# IOT_Fire_Alarm_Sheet.net
KiCad netlist of a schematic drawn in Altium Designer
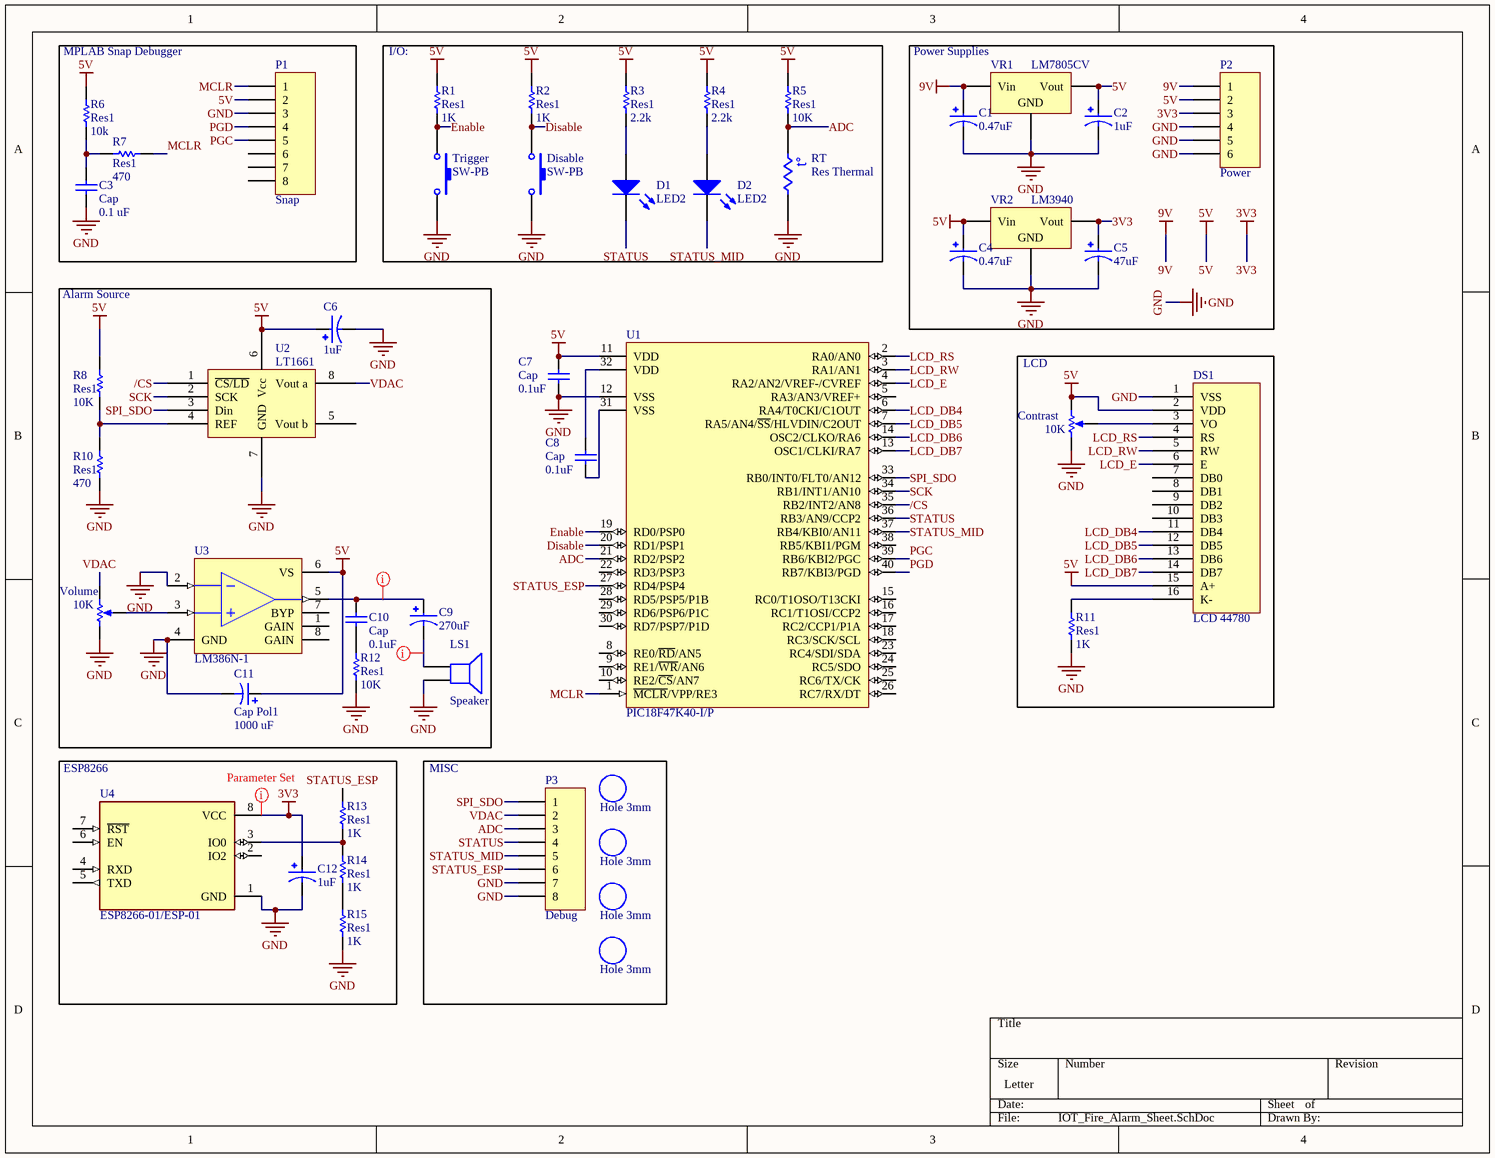
[diagram p0: IOT_Fire_Alarm_Sheet.SchDoc]

(export (version "E")
  (design (tool "Eeschema 10.0.6"))
  (components
    (comp (ref "C1")
      (value "0.47uF")
      (footprint "CAPPRD200W50D500H1500")
      (description "1F 63V Aluminum Electrolytic Capacitors Radial, Can 5000 Hrs @ 105C")
      (fields (field (name "MP") "EEU-EB1J1R0") (field (name "MF") "Panasonic Electronic Components"))
      (libsource (lib "EEUEB1J1R0") (part "EEUEB1J1R0"))
    )
    (comp (ref "C2")
      (value "1uF")
      (footprint "CAPPRD200W50D500H1500")
      (description "1F 63V Aluminum Electrolytic Capacitors Radial, Can 5000 Hrs @ 105C")
      (fields (field (name "MP") "EEU-EB1J1R0") (field (name "MF") "Panasonic Electronic Components"))
      (libsource (lib "EEUEB1J1R0") (part "EEUEB1J1R0"))
    )
    (comp (ref "C3")
      (value "Cap")
      (footprint "RAD-0.1")
      (description "Capacitor")
      (fields (field (name "ALTIUM_VALUE") "0.1 uF") (field (name "PUBLISHER") "Altium Limited"))
      (libsource (lib "Miscellaneous Devices") (part "Cap"))
    )
    (comp (ref "C4")
      (value "0.47uF")
      (footprint "CAPPRD200W50D500H1500")
      (description "1F 63V Aluminum Electrolytic Capacitors Radial, Can 5000 Hrs @ 105C")
      (fields (field (name "MP") "EEU-EB1J1R0") (field (name "MF") "Panasonic Electronic Components"))
      (libsource (lib "EEUEB1J1R0") (part "EEUEB1J1R0"))
    )
    (comp (ref "C5")
      (value "47uF")
      (footprint "CAPPRD200W50D500H1500")
      (description "1F 63V Aluminum Electrolytic Capacitors Radial, Can 5000 Hrs @ 105C")
      (fields (field (name "MP") "EEU-EB1J1R0") (field (name "MF") "Panasonic Electronic Components"))
      (libsource (lib "EEUEB1J1R0") (part "EEUEB1J1R0"))
    )
    (comp (ref "C6")
      (value "1uF")
      (footprint "CAPPRD200W50D500H1500")
      (description "1F 63V Aluminum Electrolytic Capacitors Radial, Can 5000 Hrs @ 105C")
      (fields (field (name "MP") "EEU-EB1J1R0") (field (name "MF") "Panasonic Electronic Components"))
      (libsource (lib "") (part "EEUEB1J1R0_1"))
    )
    (comp (ref "C7")
      (value "Cap")
      (footprint "RAD-0.1")
      (description "Capacitor")
      (fields (field (name "ALTIUM_VALUE") "0.1uF") (field (name "PUBLISHER") "Altium Limited"))
      (libsource (lib "Miscellaneous Devices") (part "Cap"))
    )
    (comp (ref "C8")
      (value "Cap")
      (footprint "RAD-0.1")
      (description "Capacitor")
      (fields (field (name "ALTIUM_VALUE") "0.1uF") (field (name "PUBLISHER") "Altium Limited"))
      (libsource (lib "Miscellaneous Devices") (part "Cap"))
    )
    (comp (ref "C9")
      (value "270uF")
      (footprint "CAPPRD500W60D1000H1250")
      (description "Capacitor; Aluminum Electrolytic; Radial Al Electrolytic Cap; 100uF 63V")
      (fields (field (name "MF") "Panasonic Electronic") (field (name "MP") "EEU-FC1J101"))
      (libsource (lib "EEUFC1J101") (part "EEUFC1J101"))
    )
    (comp (ref "C10")
      (value "Cap")
      (footprint "RAD-0.1")
      (description "Capacitor")
      (fields (field (name "ALTIUM_VALUE") "0.1uF") (field (name "PUBLISHER") "Altium Limited"))
      (libsource (lib "Miscellaneous Devices") (part "Cap"))
    )
    (comp (ref "C11")
      (value "Cap Pol1")
      (footprint "RB7.6-15")
      (description "Polarized Capacitor (Radial)")
      (fields (field (name "ALTIUM_VALUE") "1000 uF") (field (name "PUBLISHER") "Altium Limited"))
      (libsource (lib "Miscellaneous Devices") (part "Cap Pol1"))
    )
    (comp (ref "C12")
      (value "1uF")
      (footprint "CAPPRD200W50D500H1500")
      (description "1F 63V Aluminum Electrolytic Capacitors Radial, Can 5000 Hrs @ 105C")
      (fields (field (name "MP") "EEU-EB1J1R0") (field (name "MF") "Panasonic Electronic Components"))
      (libsource (lib "EEUEB1J1R0") (part "EEUEB1J1R0"))
    )
    (comp (ref "Contrast")
      (value "10K")
      (footprint "POT inline wide")
      (description "Potentiometer")
      (fields (field (name "Comment") "RPot_3") (field (name "PUBLISHER") "Altium Limited"))
      (libsource (lib "ECE LIB 21") (part "RPot"))
    )
    (comp (ref "D1")
      (value "LED2")
      (footprint "LED-1")
      (description "Typical RED, GREEN, YELLOW, AMBER GaAs LED")
      (fields (field (name "PUBLISHER") "Altium Limited"))
      (libsource (lib "Miscellaneous Devices") (part "LED2"))
    )
    (comp (ref "D2")
      (value "LED2")
      (footprint "LED-1")
      (description "Typical RED, GREEN, YELLOW, AMBER GaAs LED")
      (fields (field (name "PUBLISHER") "Altium Limited"))
      (libsource (lib "Miscellaneous Devices") (part "LED2"))
    )
    (comp (ref "Disable")
      (value "SW-PB")
      (footprint "SW PB")
      (description "DIGIKEY SW400-ND")
      (fields (field (name "PUBLISHER") "Altium Limited"))
      (libsource (lib "ECE LIB 21") (part "SW-PB"))
    )
    (comp (ref "DS1")
      (value "LCD 44780")
      (footprint "OLED 16x2")
      (libsource (lib "ECE LIB 21") (part "LCD 44780"))
    )
    (comp (ref "H1")
      (value "Hole 3mm")
      (footprint "Hole 3mm")
      (libsource (lib "ECE LIB 21") (part "Hole 3mm"))
    )
    (comp (ref "H2")
      (value "Hole 3mm")
      (footprint "Hole 3mm")
      (libsource (lib "ECE LIB 21") (part "Hole 3mm"))
    )
    (comp (ref "H3")
      (value "Hole 3mm")
      (footprint "Hole 3mm")
      (libsource (lib "ECE LIB 21") (part "Hole 3mm"))
    )
    (comp (ref "H4")
      (value "Hole 3mm")
      (footprint "Hole 3mm")
      (libsource (lib "ECE LIB 21") (part "Hole 3mm"))
    )
    (comp (ref "LS1")
      (value "Speaker")
      (footprint "PIN2")
      (description "Loudspeaker")
      (fields (field (name "PUBLISHER") "Altium Limited"))
      (libsource (lib "Miscellaneous Devices") (part "Speaker"))
    )
    (comp (ref "P1")
      (value "Snap")
      (footprint "HDR1X8")
      (description "Header, 8-Pin")
      (fields (field (name "PUBLISHER") "Altium Limited"))
      (libsource (lib "Miscellaneous Connectors") (part "Header 8"))
    )
    (comp (ref "P2")
      (value "Power")
      (footprint "HDR1X6")
      (description "Header, 6-Pin")
      (fields (field (name "PUBLISHER") "Altium Limited"))
      (libsource (lib "Miscellaneous Connectors") (part "Header 6"))
    )
    (comp (ref "P3")
      (value "Debug")
      (footprint "HDR1X8")
      (description "Header, 8-Pin")
      (fields (field (name "PUBLISHER") "Altium Limited"))
      (libsource (lib "Miscellaneous Connectors") (part "Header 8"))
    )
    (comp (ref "R1")
      (value "Res1")
      (footprint "AXIAL-0.3")
      (description "Resistor")
      (fields (field (name "ALTIUM_VALUE") "1K") (field (name "PUBLISHER") "Altium Limited"))
      (libsource (lib "Miscellaneous Devices") (part "Res1"))
    )
    (comp (ref "R2")
      (value "Res1")
      (footprint "AXIAL-0.3")
      (description "Resistor")
      (fields (field (name "ALTIUM_VALUE") "1K") (field (name "PUBLISHER") "Altium Limited"))
      (libsource (lib "Miscellaneous Devices") (part "Res1"))
    )
    (comp (ref "R3")
      (value "Res1")
      (footprint "AXIAL-0.3")
      (description "Resistor")
      (fields (field (name "ALTIUM_VALUE") "2.2k") (field (name "PUBLISHER") "Altium Limited"))
      (libsource (lib "Miscellaneous Devices") (part "Res1"))
    )
    (comp (ref "R4")
      (value "Res1")
      (footprint "AXIAL-0.3")
      (description "Resistor")
      (fields (field (name "ALTIUM_VALUE") "2.2k") (field (name "PUBLISHER") "Altium Limited"))
      (libsource (lib "Miscellaneous Devices") (part "Res1"))
    )
    (comp (ref "R5")
      (value "Res1")
      (footprint "AXIAL-0.3")
      (description "Resistor")
      (fields (field (name "ALTIUM_VALUE") "10K") (field (name "PUBLISHER") "Altium Limited"))
      (libsource (lib "Miscellaneous Devices") (part "Res1"))
    )
    (comp (ref "R6")
      (value "Res1")
      (footprint "AXIAL-0.3")
      (description "Resistor")
      (fields (field (name "ALTIUM_VALUE") "10k") (field (name "PUBLISHER") "Altium Limited"))
      (libsource (lib "Miscellaneous Devices") (part "Res1"))
    )
    (comp (ref "R7")
      (value "Res1")
      (footprint "AXIAL-0.3")
      (description "Resistor")
      (fields (field (name "ALTIUM_VALUE") "470") (field (name "PUBLISHER") "Altium Limited"))
      (libsource (lib "Miscellaneous Devices") (part "Res1"))
    )
    (comp (ref "R8")
      (value "Res1")
      (footprint "AXIAL-0.3")
      (description "Resistor")
      (fields (field (name "ALTIUM_VALUE") "10K") (field (name "PUBLISHER") "Altium Limited"))
      (libsource (lib "Miscellaneous Devices") (part "Res1"))
    )
    (comp (ref "R10")
      (value "Res1")
      (footprint "AXIAL-0.3")
      (description "Resistor")
      (fields (field (name "ALTIUM_VALUE") "470") (field (name "PUBLISHER") "Altium Limited"))
      (libsource (lib "Miscellaneous Devices") (part "Res1"))
    )
    (comp (ref "R11")
      (value "Res1")
      (footprint "AXIAL-0.3")
      (description "Resistor")
      (fields (field (name "ALTIUM_VALUE") "1K") (field (name "PUBLISHER") "Altium Limited"))
      (libsource (lib "Miscellaneous Devices") (part "Res1"))
    )
    (comp (ref "R12")
      (value "Res1")
      (footprint "AXIAL-0.3")
      (description "Resistor")
      (fields (field (name "ALTIUM_VALUE") "10K") (field (name "PUBLISHER") "Altium Limited"))
      (libsource (lib "Miscellaneous Devices") (part "Res1"))
    )
    (comp (ref "R13")
      (value "Res1")
      (footprint "AXIAL-0.3")
      (description "Resistor")
      (fields (field (name "ALTIUM_VALUE") "1K") (field (name "PUBLISHER") "Altium Limited"))
      (libsource (lib "Miscellaneous Devices") (part "Res1"))
    )
    (comp (ref "R14")
      (value "Res1")
      (footprint "AXIAL-0.3")
      (description "Resistor")
      (fields (field (name "ALTIUM_VALUE") "1K") (field (name "PUBLISHER") "Altium Limited"))
      (libsource (lib "Miscellaneous Devices") (part "Res1"))
    )
    (comp (ref "R15")
      (value "Res1")
      (footprint "AXIAL-0.3")
      (description "Resistor")
      (fields (field (name "ALTIUM_VALUE") "1K") (field (name "PUBLISHER") "Altium Limited"))
      (libsource (lib "Miscellaneous Devices") (part "Res1"))
    )
    (comp (ref "RT")
      (value "Res Thermal")
      (footprint "RAD-0.2")
      (description "Thermistor")
      (fields (field (name "PUBLISHER") "Altium Limited"))
      (libsource (lib "Miscellaneous Devices") (part "Res Thermal"))
    )
    (comp (ref "Trigger")
      (value "SW-PB")
      (footprint "SW PB")
      (description "DIGIKEY SW400-ND")
      (fields (field (name "PUBLISHER") "Altium Limited"))
      (libsource (lib "ECE LIB 21") (part "SW-PB"))
    )
    (comp (ref "U1")
      (value "PIC18F47K40-I/P")
      (footprint "DIP-40")
      (libsource (lib "ECE LIB 21") (part "PIC18F4620-I/P_1"))
    )
    (comp (ref "U2") (value "LT1661") (footprint "DIP-8") (libsource (lib "ECE LIB 21") (part "LT1661")))
    (comp (ref "U3")
      (value "LM386N-1")
      (footprint "DIP-8")
      (description "Low-Voltage Audio Power Amplifier")
      (fields (field (name "PUBLISHER") "Altium Limited"))
      (libsource (lib "ECE LIB 21") (part "LM386N-1"))
    )
    (comp (ref "U4")
      (value "ESP8266-01/ESP-01")
      (footprint "XCVR_ESP8266-01/ESP-01")
      (fields (field (name "MF") "AI-Thinker"))
      (libsource (lib "ESP8266-01_ESP-01") (part "ESP8266-01/ESP-01"))
    )
    (comp (ref "Volume")
      (value "10K")
      (footprint "POT inline wide")
      (description "Potentiometer")
      (fields (field (name "Comment") "RPot_3") (field (name "PUBLISHER") "Altium Limited"))
      (libsource (lib "ECE LIB 21") (part "RPot"))
    )
    (comp (ref "VR1")
      (value "LM7805CV")
      (footprint "T03B")
      (description "Voltage Regulator")
      (fields (field (name "PUBLISHER") "Altium Limited"))
      (libsource (lib "Miscellaneous Devices") (part "Volt Reg"))
    )
    (comp (ref "VR2")
      (value "LM3940")
      (footprint "T03B")
      (description "Voltage Regulator")
      (fields (field (name "PUBLISHER") "Altium Limited"))
      (libsource (lib "Miscellaneous Devices") (part "Volt Reg"))
    )
  )
  (nets
    (net (code "1") (name "/ADC") (class "Default")
      (node (ref "P3") (pin "3") (pinfunction "3_3") (pintype "passive"))
      (node (ref "R5") (pin "1") (pinfunction "1_1") (pintype "passive"))
      (node (ref "RT") (pin "1") (pinfunction "1_1") (pintype "passive"))
      (node (ref "U1") (pin "21") (pinfunction "RD2/PSP2_21") (pintype "bidirectional"))
    )
    (net (code "2") (name "/Disable") (class "Default")
      (node (ref "Disable") (pin "1") (pinfunction "1_1") (pintype "passive"))
      (node (ref "R2") (pin "1") (pinfunction "1_1") (pintype "passive"))
      (node (ref "U1") (pin "20") (pinfunction "RD1/PSP1_20") (pintype "bidirectional"))
    )
    (net (code "3") (name "/Enable") (class "Default")
      (node (ref "R1") (pin "1") (pinfunction "1_1") (pintype "passive"))
      (node (ref "Trigger") (pin "1") (pinfunction "1_1") (pintype "passive"))
      (node (ref "U1") (pin "19") (pinfunction "RD0/PSP0_19") (pintype "bidirectional"))
    )
    (net (code "4") (name "/LCD_DB4") (class "Default")
      (node (ref "DS1") (pin "11") (pinfunction "DB4_11") (pintype "passive"))
      (node (ref "U1") (pin "6") (pinfunction "RA4/T0CKI/C1OUT_6") (pintype "bidirectional"))
    )
    (net (code "5") (name "/LCD_DB5") (class "Default")
      (node (ref "DS1") (pin "12") (pinfunction "DB5_12") (pintype "passive"))
      (node (ref "U1") (pin "7") (pinfunction "RA5/AN4/~{SS}/HLVDIN/C2OUT_7") (pintype "bidirectional"))
    )
    (net (code "6") (name "/LCD_DB6") (class "Default")
      (node (ref "DS1") (pin "13") (pinfunction "DB6_13") (pintype "passive"))
      (node (ref "U1") (pin "14") (pinfunction "OSC2/CLKO/RA6_14") (pintype "bidirectional"))
    )
    (net (code "7") (name "/LCD_DB7") (class "Default")
      (node (ref "DS1") (pin "14") (pinfunction "DB7_14") (pintype "passive"))
      (node (ref "U1") (pin "13") (pinfunction "OSC1/CLKI/RA7_13") (pintype "bidirectional"))
    )
    (net (code "8") (name "/LCD_E") (class "Default")
      (node (ref "DS1") (pin "6") (pinfunction "E_6") (pintype "passive"))
      (node (ref "U1") (pin "4") (pinfunction "RA2/AN2/VREF-/CVREF_4") (pintype "bidirectional"))
    )
    (net (code "9") (name "/LCD_RS") (class "Default")
      (node (ref "DS1") (pin "4") (pinfunction "RS_4") (pintype "passive"))
      (node (ref "U1") (pin "2") (pinfunction "RA0/AN0_2") (pintype "bidirectional"))
    )
    (net (code "10") (name "/LCD_RW") (class "Default")
      (node (ref "DS1") (pin "5") (pinfunction "RW_5") (pintype "passive"))
      (node (ref "U1") (pin "3") (pinfunction "RA1/AN1_3") (pintype "bidirectional"))
    )
    (net (code "11") (name "/MCLR") (class "Default")
      (node (ref "P1") (pin "1") (pinfunction "1_1") (pintype "passive"))
      (node (ref "R7") (pin "2") (pinfunction "2_2") (pintype "passive"))
      (node (ref "U1") (pin "1") (pinfunction "~{MCLR}/VPP/RE3_1") (pintype "input"))
    )
    (net (code "12") (name "/PGC") (class "Default")
      (node (ref "P1") (pin "5") (pinfunction "5_5") (pintype "passive"))
      (node (ref "U1") (pin "39") (pinfunction "RB6/KBI2/PGC_39") (pintype "bidirectional"))
    )
    (net (code "13") (name "/PGD") (class "Default")
      (node (ref "P1") (pin "4") (pinfunction "4_4") (pintype "passive"))
      (node (ref "U1") (pin "40") (pinfunction "RB7/KBI3/PGD_40") (pintype "bidirectional"))
    )
    (net (code "14") (name "/SCK") (class "Default")
      (node (ref "U1") (pin "34") (pinfunction "RB1/INT1/AN10_34") (pintype "bidirectional"))
      (node (ref "U2") (pin "2") (pinfunction "SCK_2") (pintype "passive"))
    )
    (net (code "15") (name "/SPI_SDO") (class "Default")
      (node (ref "P3") (pin "1") (pinfunction "1_1") (pintype "passive"))
      (node (ref "U1") (pin "33") (pinfunction "RB0/INT0/FLT0/AN12_33") (pintype "bidirectional"))
      (node (ref "U2") (pin "3") (pinfunction "Din_3") (pintype "passive"))
    )
    (net (code "16") (name "/STATUS") (class "Default")
      (node (ref "D1") (pin "2") (pinfunction "K_2") (pintype "passive"))
      (node (ref "P3") (pin "4") (pinfunction "4_4") (pintype "passive"))
      (node (ref "U1") (pin "36") (pinfunction "RB3/AN9/CCP2_36") (pintype "bidirectional"))
    )
    (net (code "17") (name "/STATUS_ESP") (class "Default")
      (node (ref "P3") (pin "6") (pinfunction "6_6") (pintype "passive"))
      (node (ref "R13") (pin "2") (pinfunction "2_2") (pintype "passive"))
      (node (ref "U1") (pin "27") (pinfunction "RD4/PSP4_27") (pintype "bidirectional"))
    )
    (net (code "18") (name "/STATUS_MID") (class "Default")
      (node (ref "D2") (pin "2") (pinfunction "K_2") (pintype "passive"))
      (node (ref "P3") (pin "5") (pinfunction "5_5") (pintype "passive"))
      (node (ref "U1") (pin "37") (pinfunction "RB4/KBI0/AN11_37") (pintype "bidirectional"))
    )
    (net (code "19") (name "/VDAC") (class "Default")
      (node (ref "P3") (pin "2") (pinfunction "2_2") (pintype "passive"))
      (node (ref "U2") (pin "8") (pinfunction "Vout_a_8") (pintype "passive"))
      (node (ref "Volume") (pin "3") (pinfunction "BOT_3") (pintype "passive"))
    )
    (net (code "20") (name "/{slash}CS") (class "Default")
      (node (ref "U1") (pin "35") (pinfunction "RB2/INT2/AN8_35") (pintype "bidirectional"))
      (node (ref "U2") (pin "1") (pinfunction "~{CS/LD}_1") (pintype "passive"))
    )
    (net (code "21") (name "3V3") (class "Default")
      (node (ref "C12") (pin "P") (pinfunction "P_P") (pintype "passive"))
      (node (ref "C5") (pin "P") (pinfunction "P_P") (pintype "passive"))
      (node (ref "P2") (pin "3") (pinfunction "3_3") (pintype "passive"))
      (node (ref "U4") (pin "8") (pinfunction "VCC_8") (pintype "power_in"))
      (node (ref "VR2") (pin "3") (pinfunction "Vout_3") (pintype "passive"))
    )
    (net (code "22") (name "5V") (class "Default")
      (node (ref "C11") (pin "1") (pinfunction "1_1") (pintype "passive"))
      (node (ref "C2") (pin "P") (pinfunction "P_P") (pintype "passive"))
      (node (ref "C4") (pin "P") (pinfunction "P_P") (pintype "passive"))
      (node (ref "C6") (pin "P") (pinfunction "P_P") (pintype "passive"))
      (node (ref "C7") (pin "2") (pinfunction "2_2") (pintype "passive"))
      (node (ref "Contrast") (pin "3") (pinfunction "BOT_3") (pintype "passive"))
      (node (ref "DS1") (pin "15") (pinfunction "A+_15") (pintype "passive"))
      (node (ref "DS1") (pin "2") (pinfunction "VDD_2") (pintype "passive"))
      (node (ref "P1") (pin "2") (pinfunction "2_2") (pintype "passive"))
      (node (ref "P2") (pin "2") (pinfunction "2_2") (pintype "passive"))
      (node (ref "R1") (pin "2") (pinfunction "2_2") (pintype "passive"))
      (node (ref "R2") (pin "2") (pinfunction "2_2") (pintype "passive"))
      (node (ref "R3") (pin "2") (pinfunction "2_2") (pintype "passive"))
      (node (ref "R4") (pin "2") (pinfunction "2_2") (pintype "passive"))
      (node (ref "R5") (pin "2") (pinfunction "2_2") (pintype "passive"))
      (node (ref "R6") (pin "2") (pinfunction "2_2") (pintype "passive"))
      (node (ref "R8") (pin "1") (pinfunction "1_1") (pintype "passive"))
      (node (ref "U1") (pin "11") (pinfunction "VDD_11") (pintype "power_in"))
      (node (ref "U2") (pin "6") (pinfunction "Vcc_6") (pintype "passive"))
      (node (ref "U3") (pin "6") (pinfunction "VS_6") (pintype "power_in"))
      (node (ref "VR1") (pin "3") (pinfunction "Vout_3") (pintype "passive"))
      (node (ref "VR2") (pin "1") (pinfunction "Vin_1") (pintype "passive"))
    )
    (net (code "23") (name "9V") (class "Default")
      (node (ref "C1") (pin "P") (pinfunction "P_P") (pintype "passive"))
      (node (ref "P2") (pin "1") (pinfunction "1_1") (pintype "passive"))
      (node (ref "VR1") (pin "1") (pinfunction "Vin_1") (pintype "passive"))
    )
    (net (code "24") (name "GND") (class "Default")
      (node (ref "C1") (pin "N") (pinfunction "N_N") (pintype "passive"))
      (node (ref "C11") (pin "2") (pinfunction "2_2") (pintype "passive"))
      (node (ref "C12") (pin "N") (pinfunction "N_N") (pintype "passive"))
      (node (ref "C2") (pin "N") (pinfunction "N_N") (pintype "passive"))
      (node (ref "C3") (pin "1") (pinfunction "1_1") (pintype "passive"))
      (node (ref "C4") (pin "N") (pinfunction "N_N") (pintype "passive"))
      (node (ref "C5") (pin "N") (pinfunction "N_N") (pintype "passive"))
      (node (ref "C6") (pin "N") (pinfunction "N_N") (pintype "passive"))
      (node (ref "C7") (pin "1") (pinfunction "1_1") (pintype "passive"))
      (node (ref "Contrast") (pin "1") (pinfunction "TOP_1") (pintype "passive"))
      (node (ref "DS1") (pin "1") (pinfunction "VSS_1") (pintype "passive"))
      (node (ref "Disable") (pin "2") (pinfunction "2_2") (pintype "passive"))
      (node (ref "LS1") (pin "2") (pinfunction "2_2") (pintype "passive"))
      (node (ref "P1") (pin "3") (pinfunction "3_3") (pintype "passive"))
      (node (ref "P2") (pin "4") (pinfunction "4_4") (pintype "passive"))
      (node (ref "P2") (pin "5") (pinfunction "5_5") (pintype "passive"))
      (node (ref "P2") (pin "6") (pinfunction "6_6") (pintype "passive"))
      (node (ref "P3") (pin "7") (pinfunction "7_7") (pintype "passive"))
      (node (ref "P3") (pin "8") (pinfunction "8_8") (pintype "passive"))
      (node (ref "R10") (pin "1") (pinfunction "1_1") (pintype "passive"))
      (node (ref "R11") (pin "1") (pinfunction "1_1") (pintype "passive"))
      (node (ref "R12") (pin "1") (pinfunction "1_1") (pintype "passive"))
      (node (ref "R15") (pin "1") (pinfunction "1_1") (pintype "passive"))
      (node (ref "RT") (pin "2") (pinfunction "2_2") (pintype "passive"))
      (node (ref "Trigger") (pin "2") (pinfunction "2_2") (pintype "passive"))
      (node (ref "U1") (pin "12") (pinfunction "VSS_12") (pintype "power_in"))
      (node (ref "U2") (pin "7") (pinfunction "GND_7") (pintype "passive"))
      (node (ref "U3") (pin "2") (pinfunction "IN-_2") (pintype "input"))
      (node (ref "U3") (pin "4") (pinfunction "GND_4") (pintype "power_in"))
      (node (ref "U4") (pin "1") (pinfunction "GND_1") (pintype "power_in"))
      (node (ref "VR1") (pin "2") (pinfunction "GND_2") (pintype "passive"))
      (node (ref "VR2") (pin "2") (pinfunction "GND_2") (pintype "passive"))
      (node (ref "Volume") (pin "1") (pinfunction "TOP_1") (pintype "passive"))
    )
    (net (code "25") (name "Net-(C3-Pad2)") (class "Default")
      (node (ref "C3") (pin "2") (pinfunction "2_2") (pintype "passive"))
      (node (ref "R6") (pin "1") (pinfunction "1_1") (pintype "passive"))
      (node (ref "R7") (pin "1") (pinfunction "1_1") (pintype "passive"))
    )
    (net (code "26") (name "Net-(C8-Pad1)") (class "Default")
      (node (ref "C8") (pin "1") (pinfunction "1_1") (pintype "passive"))
      (node (ref "U1") (pin "31") (pinfunction "VSS_31") (pintype "power_in"))
    )
    (net (code "27") (name "Net-(C8-Pad2)") (class "Default")
      (node (ref "C8") (pin "2") (pinfunction "2_2") (pintype "passive"))
      (node (ref "U1") (pin "32") (pinfunction "VDD_32") (pintype "power_in"))
    )
    (net (code "28") (name "Net-(C9-PadN)") (class "Default")
      (node (ref "C9") (pin "N") (pinfunction "N_N") (pintype "passive"))
      (node (ref "LS1") (pin "1") (pinfunction "1_1") (pintype "passive"))
    )
    (net (code "29") (name "Net-(C10-Pad1)") (class "Default")
      (node (ref "C10") (pin "1") (pinfunction "1_1") (pintype "passive"))
      (node (ref "R12") (pin "2") (pinfunction "2_2") (pintype "passive"))
    )
    (net (code "30") (name "Net-(Contrast-TAP)") (class "Default")
      (node (ref "Contrast") (pin "2") (pinfunction "TAP_2") (pintype "passive"))
      (node (ref "DS1") (pin "3") (pinfunction "VO_3") (pintype "passive"))
    )
    (net (code "31") (name "Net-(D1-A)") (class "Default")
      (node (ref "D1") (pin "1") (pinfunction "A_1") (pintype "passive"))
      (node (ref "R3") (pin "1") (pinfunction "1_1") (pintype "passive"))
    )
    (net (code "32") (name "Net-(D2-A)") (class "Default")
      (node (ref "D2") (pin "1") (pinfunction "A_1") (pintype "passive"))
      (node (ref "R4") (pin "1") (pinfunction "1_1") (pintype "passive"))
    )
    (net (code "33") (name "Net-(DS1-K-)") (class "Default")
      (node (ref "DS1") (pin "16") (pinfunction "K-_16") (pintype "passive"))
      (node (ref "R11") (pin "2") (pinfunction "2_2") (pintype "passive"))
    )
    (net (code "34") (name "Net-(R14-Pad1)") (class "Default")
      (node (ref "R14") (pin "1") (pinfunction "1_1") (pintype "passive"))
      (node (ref "R15") (pin "2") (pinfunction "2_2") (pintype "passive"))
    )
    (net (code "35") (name "Net-(U2-REF)") (class "Default")
      (node (ref "R10") (pin "2") (pinfunction "2_2") (pintype "passive"))
      (node (ref "R8") (pin "2") (pinfunction "2_2") (pintype "passive"))
      (node (ref "U2") (pin "4") (pinfunction "REF_4") (pintype "passive"))
    )
    (net (code "36") (name "Net-(U3-IN+)") (class "Default")
      (node (ref "U3") (pin "3") (pinfunction "IN+_3") (pintype "input"))
      (node (ref "Volume") (pin "2") (pinfunction "TAP_2") (pintype "passive"))
    )
    (net (code "37") (name "Net-(U3-OUT)") (class "Default")
      (node (ref "C10") (pin "2") (pinfunction "2_2") (pintype "passive"))
      (node (ref "C9") (pin "P") (pinfunction "P_P") (pintype "passive"))
      (node (ref "U3") (pin "5") (pinfunction "OUT_5") (pintype "output"))
    )
    (net (code "38") (name "Net-(U4-IO0)") (class "Default")
      (node (ref "R13") (pin "1") (pinfunction "1_1") (pintype "passive"))
      (node (ref "R14") (pin "2") (pinfunction "2_2") (pintype "passive"))
      (node (ref "U4") (pin "3") (pinfunction "IO0_3") (pintype "bidirectional"))
    )
    (net (code "39") (name "unconnected-(DS1-DB0-Pad7)") (class "Default")
      (node (ref "DS1") (pin "7") (pinfunction "DB0_7") (pintype "passive"))
    )
    (net (code "40") (name "unconnected-(DS1-DB1-Pad8)") (class "Default")
      (node (ref "DS1") (pin "8") (pinfunction "DB1_8") (pintype "passive"))
    )
    (net (code "41") (name "unconnected-(DS1-DB2-Pad9)") (class "Default")
      (node (ref "DS1") (pin "9") (pinfunction "DB2_9") (pintype "passive"))
    )
    (net (code "42") (name "unconnected-(DS1-DB3-Pad10)") (class "Default")
      (node (ref "DS1") (pin "10") (pinfunction "DB3_10") (pintype "passive"))
    )
    (net (code "43") (name "unconnected-(P1-Pad6)") (class "Default")
      (node (ref "P1") (pin "6") (pinfunction "6_6") (pintype "passive"))
    )
    (net (code "44") (name "unconnected-(P1-Pad7)") (class "Default")
      (node (ref "P1") (pin "7") (pinfunction "7_7") (pintype "passive"))
    )
    (net (code "45") (name "unconnected-(P1-Pad8)") (class "Default")
      (node (ref "P1") (pin "8") (pinfunction "8_8") (pintype "passive"))
    )
    (net (code "46") (name "unconnected-(U1-RA3{slash}AN3{slash}VREF+-Pad5)") (class "Default")
      (node (ref "U1") (pin "5") (pinfunction "RA3/AN3/VREF+_5") (pintype "bidirectional"))
    )
    (net (code "47") (name "unconnected-(U1-RB5{slash}KBI1{slash}PGM-Pad38)") (class "Default")
      (node (ref "U1") (pin "38") (pinfunction "RB5/KBI1/PGM_38") (pintype "bidirectional"))
    )
    (net (code "48") (name "unconnected-(U1-RC0{slash}T1OSO{slash}T13CKI-Pad15)") (class "Default")
      (node (ref "U1") (pin "15") (pinfunction "RC0/T1OSO/T13CKI_15") (pintype "bidirectional"))
    )
    (net (code "49") (name "unconnected-(U1-RC1{slash}T1OSI{slash}CCP2-Pad16)") (class "Default")
      (node (ref "U1") (pin "16") (pinfunction "RC1/T1OSI/CCP2_16") (pintype "bidirectional"))
    )
    (net (code "50") (name "unconnected-(U1-RC2{slash}CCP1{slash}P1A-Pad17)") (class "Default")
      (node (ref "U1") (pin "17") (pinfunction "RC2/CCP1/P1A_17") (pintype "bidirectional"))
    )
    (net (code "51") (name "unconnected-(U1-RC3{slash}SCK{slash}SCL-Pad18)") (class "Default")
      (node (ref "U1") (pin "18") (pinfunction "RC3/SCK/SCL_18") (pintype "bidirectional"))
    )
    (net (code "52") (name "unconnected-(U1-RC4{slash}SDI{slash}SDA-Pad23)") (class "Default")
      (node (ref "U1") (pin "23") (pinfunction "RC4/SDI/SDA_23") (pintype "bidirectional"))
    )
    (net (code "53") (name "unconnected-(U1-RC5{slash}SDO-Pad24)") (class "Default")
      (node (ref "U1") (pin "24") (pinfunction "RC5/SDO_24") (pintype "bidirectional"))
    )
    (net (code "54") (name "unconnected-(U1-RC6{slash}TX{slash}CK-Pad25)") (class "Default")
      (node (ref "U1") (pin "25") (pinfunction "RC6/TX/CK_25") (pintype "bidirectional"))
    )
    (net (code "55") (name "unconnected-(U1-RC7{slash}RX{slash}DT-Pad26)") (class "Default")
      (node (ref "U1") (pin "26") (pinfunction "RC7/RX/DT_26") (pintype "bidirectional"))
    )
    (net (code "56") (name "unconnected-(U1-RD3{slash}PSP3-Pad22)") (class "Default")
      (node (ref "U1") (pin "22") (pinfunction "RD3/PSP3_22") (pintype "bidirectional"))
    )
    (net (code "57") (name "unconnected-(U1-RD5{slash}PSP5{slash}P1B-Pad28)") (class "Default")
      (node (ref "U1") (pin "28") (pinfunction "RD5/PSP5/P1B_28") (pintype "bidirectional"))
    )
    (net (code "58") (name "unconnected-(U1-RD6{slash}PSP6{slash}P1C-Pad29)") (class "Default")
      (node (ref "U1") (pin "29") (pinfunction "RD6/PSP6/P1C_29") (pintype "bidirectional"))
    )
    (net (code "59") (name "unconnected-(U1-RD7{slash}PSP7{slash}P1D-Pad30)") (class "Default")
      (node (ref "U1") (pin "30") (pinfunction "RD7/PSP7/P1D_30") (pintype "bidirectional"))
    )
    (net (code "60") (name "unconnected-(U1-RE0{slash}~{RD}{slash}AN5-Pad8)") (class "Default")
      (node (ref "U1") (pin "8") (pinfunction "RE0/~{RD}/AN5_8") (pintype "bidirectional"))
    )
    (net (code "61") (name "unconnected-(U1-RE1{slash}~{WR}{slash}AN6-Pad9)") (class "Default")
      (node (ref "U1") (pin "9") (pinfunction "RE1/~{WR}/AN6_9") (pintype "bidirectional"))
    )
    (net (code "62") (name "unconnected-(U1-RE2{slash}~{CS}{slash}AN7-Pad10)") (class "Default")
      (node (ref "U1") (pin "10") (pinfunction "RE2/~{CS}/AN7_10") (pintype "bidirectional"))
    )
    (net (code "63") (name "unconnected-(U2-Vout_b-Pad5)") (class "Default")
      (node (ref "U2") (pin "5") (pinfunction "Vout_b_5") (pintype "passive"))
    )
    (net (code "64") (name "unconnected-(U3-BYP-Pad7)") (class "Default")
      (node (ref "U3") (pin "7") (pinfunction "BYP_7") (pintype "passive"))
    )
    (net (code "65") (name "unconnected-(U3-GAIN-Pad1)") (class "Default")
      (node (ref "U3") (pin "1") (pinfunction "GAIN_1") (pintype "passive"))
    )
    (net (code "66") (name "unconnected-(U3-GAIN-Pad8)") (class "Default")
      (node (ref "U3") (pin "8") (pinfunction "GAIN_8") (pintype "passive"))
    )
    (net (code "67") (name "unconnected-(U4-EN-Pad6)") (class "Default")
      (node (ref "U4") (pin "6") (pinfunction "EN_6") (pintype "input"))
    )
    (net (code "68") (name "unconnected-(U4-IO2-Pad2)") (class "Default")
      (node (ref "U4") (pin "2") (pinfunction "IO2_2") (pintype "bidirectional"))
    )
    (net (code "69") (name "unconnected-(U4-RXD-Pad4)") (class "Default")
      (node (ref "U4") (pin "4") (pinfunction "RXD_4") (pintype "input"))
    )
    (net (code "70") (name "unconnected-(U4-TXD-Pad5)") (class "Default")
      (node (ref "U4") (pin "5") (pinfunction "TXD_5") (pintype "output"))
    )
    (net (code "71") (name "unconnected-(U4-~{RST}-Pad7)") (class "Default")
      (node (ref "U4") (pin "7") (pinfunction "~{RST}_7") (pintype "input"))
    )
  )
)
